# MS5803-14BA_Breakout_v10.net
KiCad netlist of a schematic drawn in EAGLE
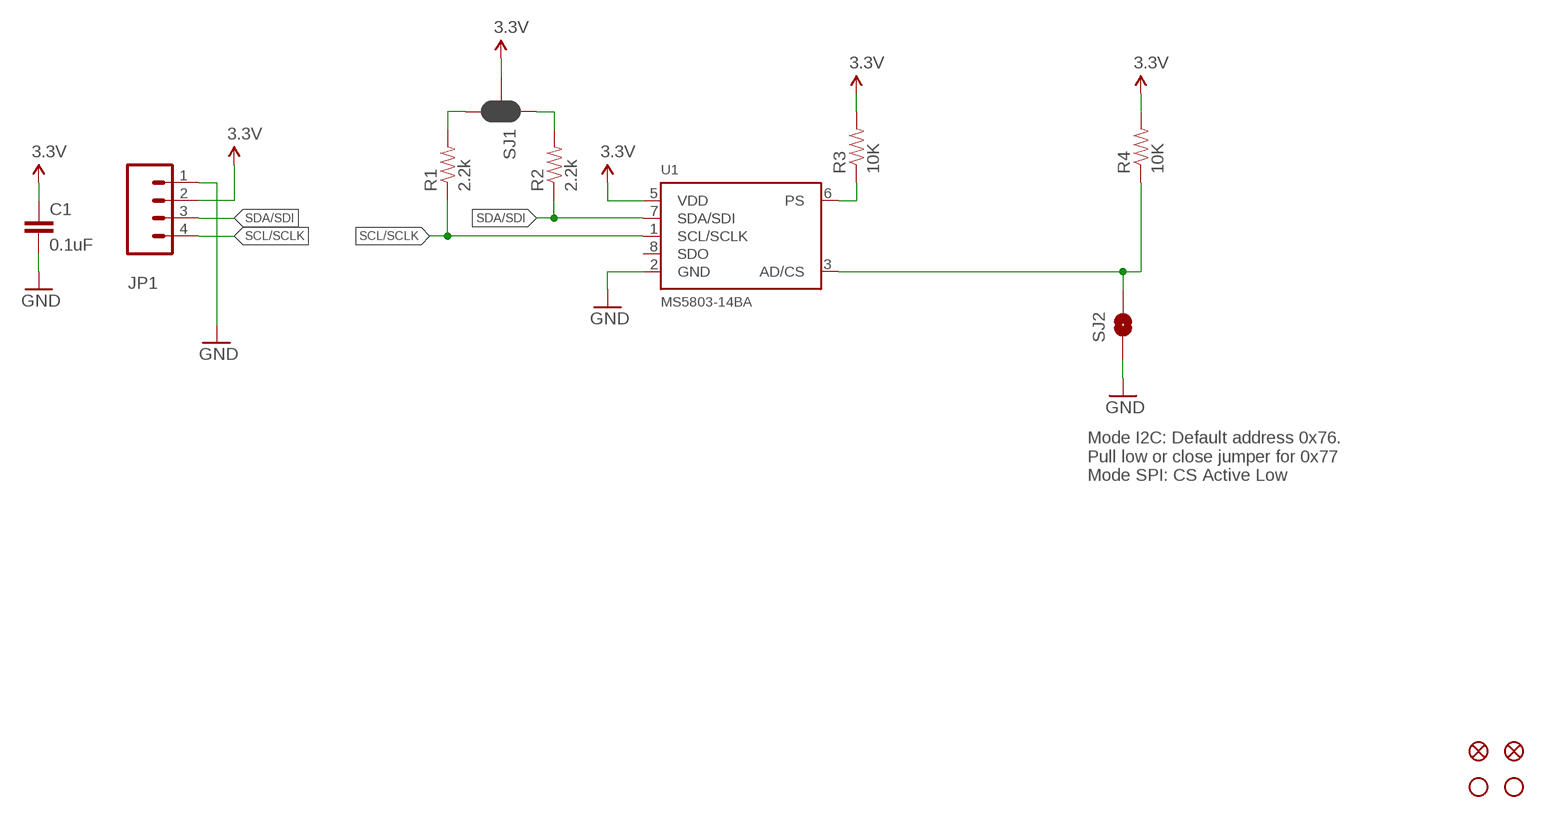
[diagram p0: schematic, sheet 1]

(export (version "E")
  (design (tool "Eeschema 10.0.6"))
  (components
    (comp (ref "C1")
      (value "0.1uF")
      (footprint "eagle-import:0603-CAP")
      (libsource (lib "eagle-import") (part "0.1UF-25V(+80/-20%)(0603)"))
    )
    (comp (ref "FID1")
      (value "FIDUCIAL1X2")
      (footprint "eagle-import:FIDUCIAL-1X2")
      (libsource (lib "eagle-import") (part "FIDUCIAL1X2"))
    )
    (comp (ref "FID2")
      (value "FIDUCIAL1X2")
      (footprint "eagle-import:FIDUCIAL-1X2")
      (libsource (lib "eagle-import") (part "FIDUCIAL1X2"))
    )
    (comp (ref "JP1")
      (value "CONN_04PTH")
      (footprint "eagle-import:1X04")
      (libsource (lib "eagle-import") (part "CONN_04PTH"))
    )
    (comp (ref "R1")
      (value "2.2k")
      (footprint "eagle-import:0603-RES")
      (libsource (lib "eagle-import") (part "2.2KOHM1/10W1%(0603)"))
    )
    (comp (ref "R2")
      (value "2.2k")
      (footprint "eagle-import:0603-RES")
      (libsource (lib "eagle-import") (part "2.2KOHM1/10W1%(0603)"))
    )
    (comp (ref "R3")
      (value "10K")
      (footprint "eagle-import:0603-RES")
      (libsource (lib "eagle-import") (part "10KOHM1/10W1%(0603)0603"))
    )
    (comp (ref "R4")
      (value "10K")
      (footprint "eagle-import:0603-RES")
      (libsource (lib "eagle-import") (part "10KOHM1/10W1%(0603)0603"))
    )
    (comp (ref "SJ1")
      (value "JUMPER-PAD-3-NC_BY_PASTE")
      (footprint "eagle-import:PAD-JUMPER-3-NC_BY_PASTE_YES_SILK_FULL_BOX")
      (libsource (lib "eagle-import") (part "JUMPER-PAD-3-NC_BY_PASTE"))
    )
    (comp (ref "SJ2")
      (value "SOLDERJUMPERNO")
      (footprint "eagle-import:SJ_2S-NO")
      (libsource (lib "eagle-import") (part "SOLDERJUMPERNO"))
    )
    (comp (ref "STANDOFF1")
      (value "STAND-OFFTIGHT")
      (footprint "eagle-import:STAND-OFF-TIGHT")
      (libsource (lib "eagle-import") (part "STAND-OFFTIGHT"))
    )
    (comp (ref "STANDOFF2")
      (value "STAND-OFFTIGHT")
      (footprint "eagle-import:STAND-OFF-TIGHT")
      (libsource (lib "eagle-import") (part "STAND-OFFTIGHT"))
    )
    (comp (ref "U1")
      (value "MS5803-14BA")
      (footprint "eagle-import:MS5803")
      (libsource (lib "eagle-import") (part "MS5803-14BA"))
    )
  )
  (nets
    (net (code "1") (name "3.3V") (class "Default")
      (node (ref "C1") (pin "1") (pinfunction "1_1") (pintype "passive"))
      (node (ref "JP1") (pin "2") (pinfunction "2_2") (pintype "passive"))
      (node (ref "R3") (pin "2") (pinfunction "2_2") (pintype "passive"))
      (node (ref "R4") (pin "2") (pinfunction "2_2") (pintype "passive"))
      (node (ref "SJ1") (pin "2") (pinfunction "2_2") (pintype "passive"))
      (node (ref "U1") (pin "5") (pinfunction "VDD_5") (pintype "bidirectional"))
    )
    (net (code "2") (name "GND") (class "Default")
      (node (ref "C1") (pin "2") (pinfunction "2_2") (pintype "passive"))
      (node (ref "JP1") (pin "1") (pinfunction "1_1") (pintype "passive"))
      (node (ref "SJ2") (pin "1") (pinfunction "1_1") (pintype "passive"))
      (node (ref "U1") (pin "2") (pinfunction "GND_2") (pintype "bidirectional"))
    )
    (net (code "3") (name "Net-(R1-Pad2)") (class "Default")
      (node (ref "R1") (pin "2") (pinfunction "2_2") (pintype "passive"))
      (node (ref "SJ1") (pin "3") (pinfunction "3_3") (pintype "passive"))
    )
    (net (code "4") (name "Net-(R2-Pad2)") (class "Default")
      (node (ref "R2") (pin "2") (pinfunction "2_2") (pintype "passive"))
      (node (ref "SJ1") (pin "1") (pinfunction "1_1") (pintype "passive"))
    )
    (net (code "5") (name "Net-(U1-AD{slash}CS)") (class "Default")
      (node (ref "R4") (pin "1") (pinfunction "1_1") (pintype "passive"))
      (node (ref "SJ2") (pin "2") (pinfunction "2_2") (pintype "passive"))
      (node (ref "U1") (pin "3") (pinfunction "AD/CS_3") (pintype "bidirectional"))
    )
    (net (code "6") (name "Net-(U1-PS)") (class "Default")
      (node (ref "R3") (pin "1") (pinfunction "1_1") (pintype "passive"))
      (node (ref "U1") (pin "6") (pinfunction "PS_6") (pintype "bidirectional"))
    )
    (net (code "7") (name "SCL{slash}SCLK") (class "Default")
      (node (ref "JP1") (pin "4") (pinfunction "4_4") (pintype "passive"))
      (node (ref "R1") (pin "1") (pinfunction "1_1") (pintype "passive"))
      (node (ref "U1") (pin "1") (pinfunction "SCL/SCLK_1") (pintype "bidirectional"))
    )
    (net (code "8") (name "SDA{slash}SDI") (class "Default")
      (node (ref "JP1") (pin "3") (pinfunction "3_3") (pintype "passive"))
      (node (ref "R2") (pin "1") (pinfunction "1_1") (pintype "passive"))
      (node (ref "U1") (pin "7") (pinfunction "SDA/SDI_7") (pintype "bidirectional"))
    )
    (net (code "9") (name "unconnected-(U1-SDO-Pad8)") (class "Default")
      (node (ref "U1") (pin "8") (pinfunction "SDO_8") (pintype "bidirectional"))
    )
  )
)
